# mini-projet.net
KiCad netlist of a schematic drawn in Altium Designer
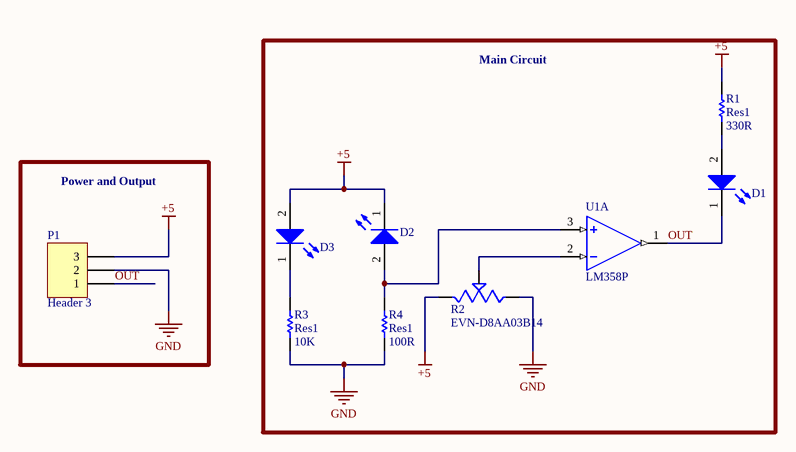
[diagram p0: mini-projet.SchDoc]

(export (version "E")
  (design (tool "Eeschema 10.0.6"))
  (components
    (comp (ref "D1")
      (value "Infrared, 1.5V, 35°")
      (footprint "WL-TIRW_D3.9H5.3")
      (description "WL-TIRW THT Infrared Round Waterclear, D3.9 x H5.3mm, 60mW/sr, Infrared, 1.5V, 35°")
      (fields
        (field (name "MANUFACTURER PART NUMBER") "15400385A3590")
        (field (name "MANUFACTURER") "Wurth Elektronik")
      )
      (libsource (lib "altium-import") (part "root_3_15400385A3590_"))
    )
    (comp (ref "D2")
      (value "Infrared, 1.5V, 35°")
      (footprint "WL-TIRW_D3.9H5.3")
      (description "WL-TIRW THT Infrared Round Waterclear, D3.9 x H5.3mm, 60mW/sr, Infrared, 1.5V, 35°")
      (fields
        (field (name "MANUFACTURER PART NUMBER") "15400385A3590")
        (field (name "MANUFACTURER") "Wurth Elektronik")
      )
      (libsource (lib "altium-import") (part "root_1_15400385A3590_"))
    )
    (comp (ref "D3")
      (value "Infrared, 1.5V, 35°")
      (footprint "WL-TIRW_D3.9H5.3")
      (description "WL-TIRW THT Infrared Round Waterclear, D3.9 x H5.3mm, 60mW/sr, Infrared, 1.5V, 35°")
      (fields
        (field (name "MANUFACTURER PART NUMBER") "15400385A3590")
        (field (name "MANUFACTURER") "Wurth Elektronik")
      )
      (libsource (lib "altium-import") (part "root_3_15400385A3590_"))
    )
    (comp (ref "P1")
      (value "Header 3")
      (footprint "HDR1X3")
      (description "Header, 3-Pin")
      (fields (field (name "PUBLISHER") "Altium Limited"))
      (libsource (lib "Miscellaneous Connectors") (part "Header 3"))
    )
    (comp (ref "R1")
      (value "Res1")
      (footprint "AXIAL-0.3")
      (description "Resistor")
      (fields (field (name "ALTIUM_VALUE") "330R") (field (name "PUBLISHER") "Altium Limited"))
      (libsource (lib "Miscellaneous Devices") (part "Res1"))
    )
    (comp (ref "R2")
      (value "EVN-D8AA03B14")
      (footprint "TRIM_EVN-D8AA03B14")
      (description "10 kOhms 0.1W, 1/10W PC Pins Through Hole Trimmer Potentiometer Carbon 1.0 Turn Top Adjustment")
      (fields (field (name "MF") "Panasonic Electronic"))
      (libsource (lib "altium-import") (part "root_2_EVN-D8AA03B14_"))
    )
    (comp (ref "R3")
      (value "Res1")
      (footprint "AXIAL-0.3")
      (description "Resistor")
      (fields (field (name "ALTIUM_VALUE") "10K") (field (name "PUBLISHER") "Altium Limited"))
      (libsource (lib "Miscellaneous Devices") (part "Res1"))
    )
    (comp (ref "R4")
      (value "Res1")
      (footprint "AXIAL-0.3")
      (description "Resistor")
      (fields (field (name "ALTIUM_VALUE") "100R") (field (name "PUBLISHER") "Altium Limited"))
      (libsource (lib "Miscellaneous Devices") (part "Res1"))
    )
    (comp (ref "U1")
      (value "LM358P")
      (footprint "DIP794W45P254L959H508Q8")
      (description "Dual, 30-V, 700-kHz operational amplifier")
      (fields (field (name "MF") "Texas Instruments"))
      (libsource (lib "altium-import") (part "root_0_LM358P_"))
    )
  )
  (nets
    (net (code "1") (name "+5") (class "Default")
      (node (ref "D2") (pin "1") (pinfunction "K_1") (pintype "passive"))
      (node (ref "D3") (pin "2") (pinfunction "A_2") (pintype "passive"))
      (node (ref "P1") (pin "3") (pinfunction "3_3") (pintype "passive"))
      (node (ref "R1") (pin "2") (pinfunction "2_2") (pintype "passive"))
      (node (ref "R2") (pin "3") (pinfunction "3_3") (pintype "passive"))
    )
    (net (code "2") (name "/OUT") (class "Default")
      (node (ref "D1") (pin "1") (pinfunction "K_1") (pintype "passive"))
      (node (ref "P1") (pin "1") (pinfunction "1_1") (pintype "passive"))
      (node (ref "U1") (pin "1") (pinfunction "OUT1_1") (pintype "output"))
    )
    (net (code "3") (name "GND") (class "Default")
      (node (ref "P1") (pin "2") (pinfunction "2_2") (pintype "passive"))
      (node (ref "R2") (pin "1") (pinfunction "1_1") (pintype "passive"))
      (node (ref "R3") (pin "1") (pinfunction "1_1") (pintype "passive"))
      (node (ref "R4") (pin "1") (pinfunction "1_1") (pintype "passive"))
    )
    (net (code "4") (name "Net-(D1-A)") (class "Default")
      (node (ref "D1") (pin "2") (pinfunction "A_2") (pintype "passive"))
      (node (ref "R1") (pin "1") (pinfunction "1_1") (pintype "passive"))
    )
    (net (code "5") (name "Net-(D2-A)") (class "Default")
      (node (ref "D2") (pin "2") (pinfunction "A_2") (pintype "passive"))
      (node (ref "R4") (pin "2") (pinfunction "2_2") (pintype "passive"))
      (node (ref "U1") (pin "3") (pinfunction "+IN1_3") (pintype "input"))
    )
    (net (code "6") (name "Net-(D3-K)") (class "Default")
      (node (ref "D3") (pin "1") (pinfunction "K_1") (pintype "passive"))
      (node (ref "R3") (pin "2") (pinfunction "2_2") (pintype "passive"))
    )
    (net (code "7") (name "Net-(U1A--IN1)") (class "Default")
      (node (ref "R2") (pin "2") (pinfunction "2_2") (pintype "passive"))
      (node (ref "U1") (pin "2") (pinfunction "-IN1_2") (pintype "input"))
    )
  )
)
